# fitnessBuddy-BOTTOM.net
KiCad netlist of a schematic drawn in EAGLE
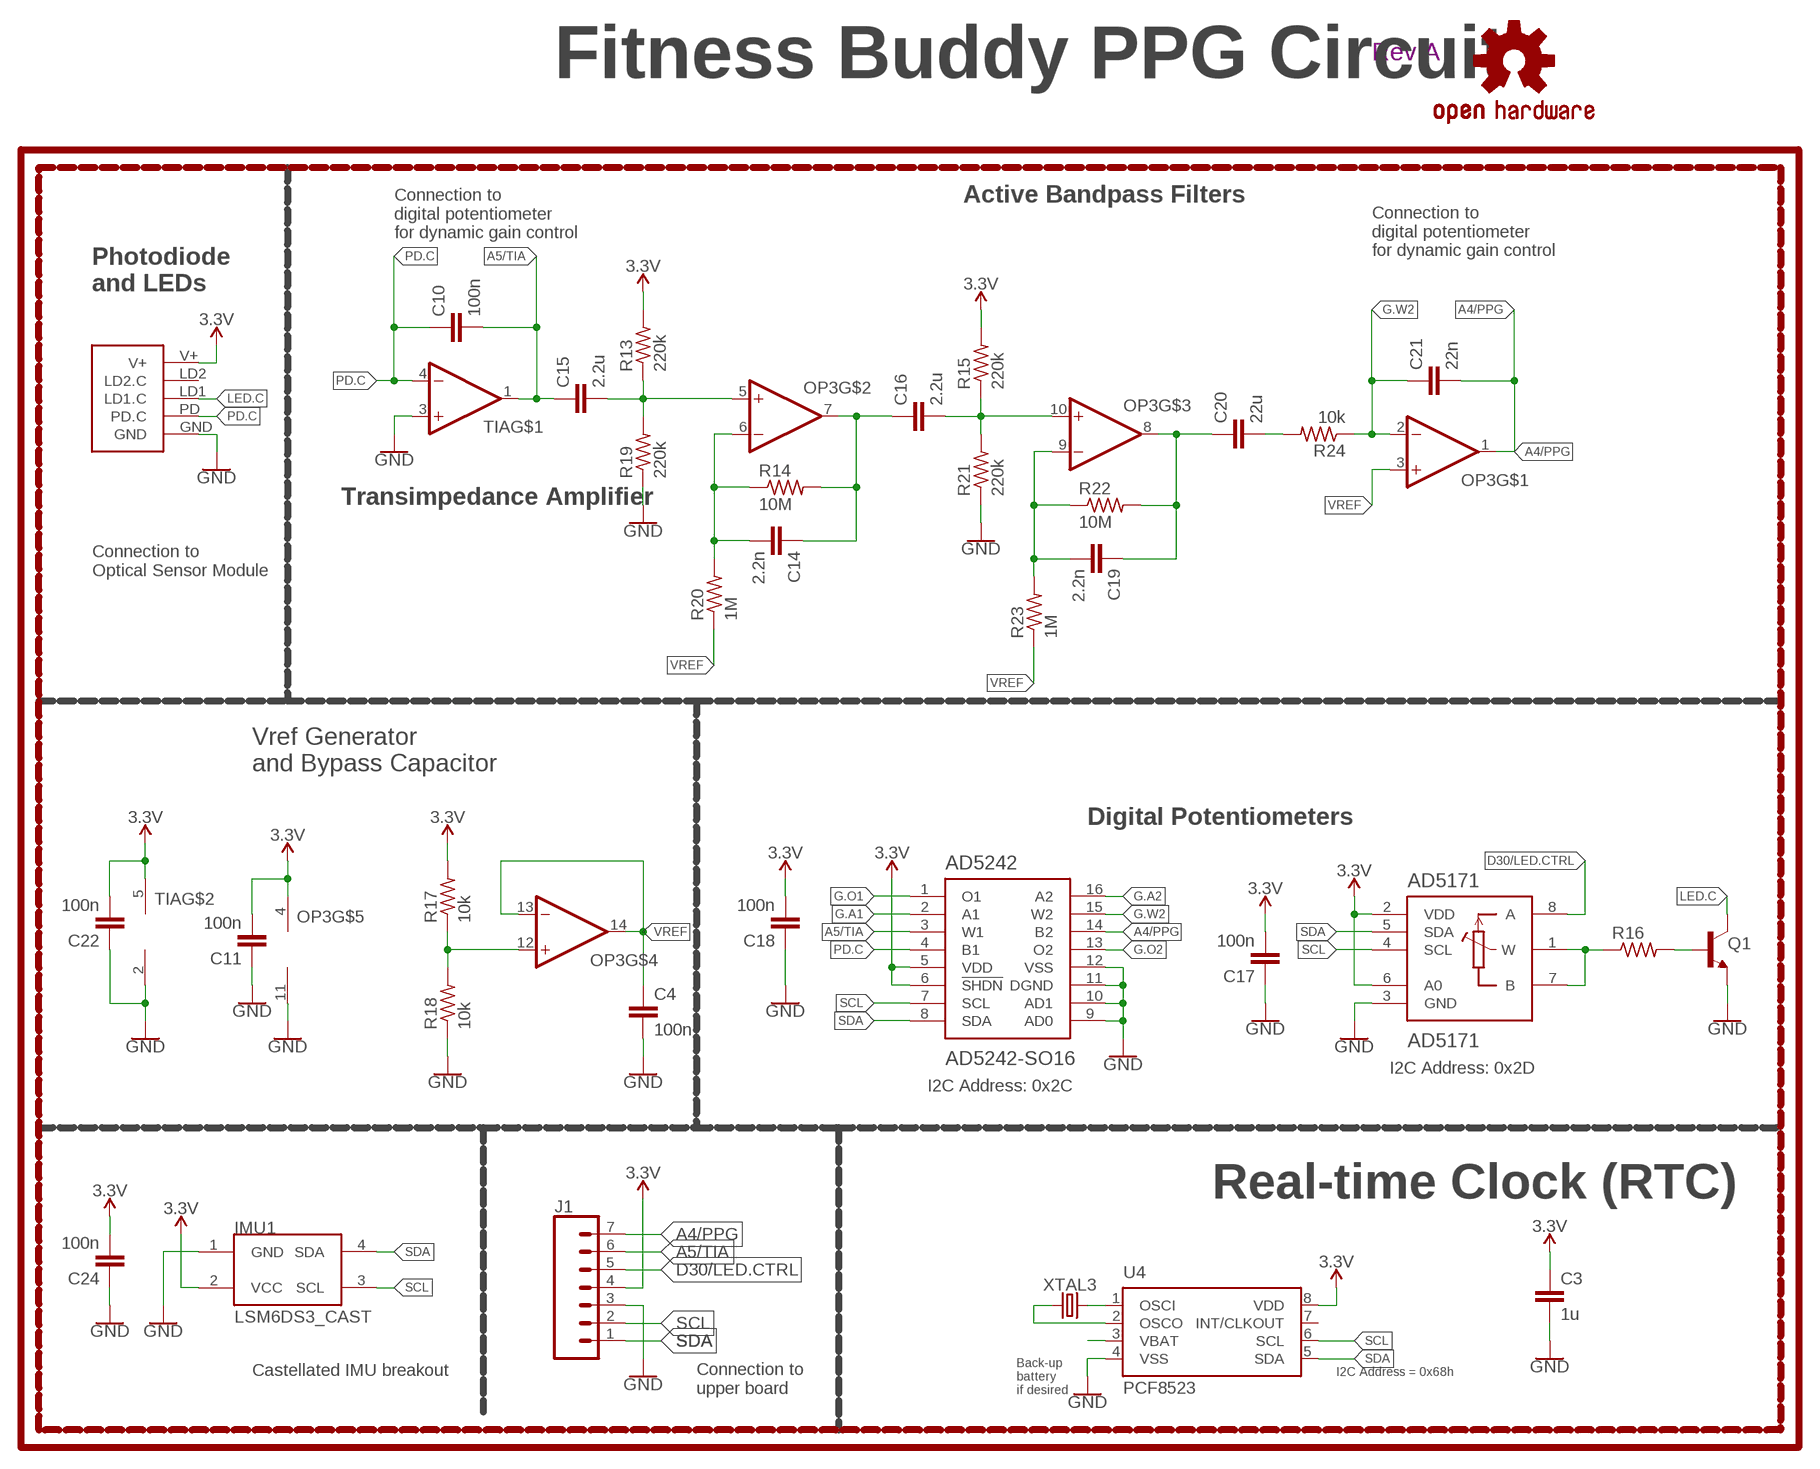
[diagram p0: schematic, sheet 1]

(export (version "E")
  (design (tool "Eeschema 10.0.6"))
  (components
    (comp (ref "AD5171")
      (value "AD5171")
      (footprint "eagle-import:SOT-23-8")
      (libsource (lib "eagle-import") (part "AD5171"))
    )
    (comp (ref "AD5242")
      (value "AD5242-SO16")
      (footprint "eagle-import:SO16")
      (libsource (lib "eagle-import") (part "AD5242-SO16"))
    )
    (comp (ref "C3")
      (value "1u")
      (footprint "eagle-import:C0603")
      (libsource (lib "eagle-import") (part "CAPACITOR0603"))
    )
    (comp (ref "C4")
      (value "100n")
      (footprint "eagle-import:C0603")
      (libsource (lib "eagle-import") (part "CAPACITOR0603"))
    )
    (comp (ref "C10")
      (value "100n")
      (footprint "eagle-import:C0603")
      (libsource (lib "eagle-import") (part "CAPACITOR0603"))
    )
    (comp (ref "C11")
      (value "100n")
      (footprint "eagle-import:C0603")
      (libsource (lib "eagle-import") (part "CAPACITOR0603"))
    )
    (comp (ref "C14")
      (value "2.2n")
      (footprint "eagle-import:C0603")
      (libsource (lib "eagle-import") (part "CAPACITOR0603"))
    )
    (comp (ref "C15")
      (value "2.2u")
      (footprint "eagle-import:C0603")
      (libsource (lib "eagle-import") (part "CAPACITOR0603"))
    )
    (comp (ref "C16")
      (value "2.2u")
      (footprint "eagle-import:C0603")
      (libsource (lib "eagle-import") (part "CAPACITOR0603"))
    )
    (comp (ref "C17")
      (value "100n")
      (footprint "eagle-import:C0603")
      (libsource (lib "eagle-import") (part "CAPACITOR0603"))
    )
    (comp (ref "C18")
      (value "100n")
      (footprint "eagle-import:C0603")
      (libsource (lib "eagle-import") (part "CAPACITOR0603"))
    )
    (comp (ref "C19")
      (value "2.2n")
      (footprint "eagle-import:C0603")
      (libsource (lib "eagle-import") (part "CAPACITOR0603"))
    )
    (comp (ref "C20")
      (value "22u")
      (footprint "eagle-import:C0603")
      (libsource (lib "eagle-import") (part "CAPACITOR0603"))
    )
    (comp (ref "C21")
      (value "22n")
      (footprint "eagle-import:C0603")
      (libsource (lib "eagle-import") (part "CAPACITOR0603"))
    )
    (comp (ref "C22")
      (value "100n")
      (footprint "eagle-import:C0603")
      (libsource (lib "eagle-import") (part "CAPACITOR0603"))
    )
    (comp (ref "C24")
      (value "100n")
      (footprint "eagle-import:C0603")
      (libsource (lib "eagle-import") (part "CAPACITOR0603"))
    )
    (comp (ref "IMU1")
      (value "LSM6DS3_CAST")
      (footprint "eagle-import:LSM6DS3_CAST")
      (libsource (lib "eagle-import") (part "LSM6DS3_CAST"))
    )
    (comp (ref "J1")
      (value "CONN_07-1.27MM")
      (footprint "eagle-import:1X07_1.27MM")
      (libsource (lib "eagle-import") (part "CONN_07-1.27MM"))
    )
    (comp (ref "LOGO1")
      (value "REVISION.A")
      (footprint "eagle-import:REV.A")
      (libsource (lib "eagle-import") (part "REVISION.A"))
    )
    (comp (ref "LOGO2")
      (value "OSHW-LOGOS")
      (footprint "eagle-import:OSHW-LOGO-S")
      (libsource (lib "eagle-import") (part "OSHW-LOGOS"))
    )
    (comp (ref "OP3")
      (value "OP-QUAD-SO14")
      (footprint "eagle-import:SO14")
      (libsource (lib "eagle-import") (part "OP-QUAD-SO14"))
    )
    (comp (ref "Q1")
      (value "NPN-GENERIC")
      (footprint "eagle-import:SOT23-3")
      (libsource (lib "eagle-import") (part "NPN-GENERIC"))
    )
    (comp (ref "R13")
      (value "220k")
      (footprint "eagle-import:R0603")
      (libsource (lib "eagle-import") (part "RESISTOR0603"))
    )
    (comp (ref "R14")
      (value "10M")
      (footprint "eagle-import:R0603")
      (libsource (lib "eagle-import") (part "RESISTOR0603"))
    )
    (comp (ref "R15")
      (value "220k")
      (footprint "eagle-import:R0603")
      (libsource (lib "eagle-import") (part "RESISTOR0603"))
    )
    (comp (ref "R16")
      (value "RESISTOR0603")
      (footprint "eagle-import:R0603")
      (libsource (lib "eagle-import") (part "RESISTOR0603"))
    )
    (comp (ref "R17")
      (value "10k")
      (footprint "eagle-import:R0402")
      (libsource (lib "eagle-import") (part "RESISTOR0402"))
    )
    (comp (ref "R18")
      (value "10k")
      (footprint "eagle-import:R0402")
      (libsource (lib "eagle-import") (part "RESISTOR0402"))
    )
    (comp (ref "R19")
      (value "220k")
      (footprint "eagle-import:R0603")
      (libsource (lib "eagle-import") (part "RESISTOR0603"))
    )
    (comp (ref "R20")
      (value "1M")
      (footprint "eagle-import:R0603")
      (libsource (lib "eagle-import") (part "RESISTOR0603"))
    )
    (comp (ref "R21")
      (value "220k")
      (footprint "eagle-import:R0603")
      (libsource (lib "eagle-import") (part "RESISTOR0603"))
    )
    (comp (ref "R22")
      (value "10M")
      (footprint "eagle-import:R0603")
      (libsource (lib "eagle-import") (part "RESISTOR0603"))
    )
    (comp (ref "R23")
      (value "1M")
      (footprint "eagle-import:R0603")
      (libsource (lib "eagle-import") (part "RESISTOR0603"))
    )
    (comp (ref "R24")
      (value "10k")
      (footprint "eagle-import:R0603")
      (libsource (lib "eagle-import") (part "RESISTOR0603"))
    )
    (comp (ref "TIA")
      (value "OP-SINGLEOT")
      (footprint "eagle-import:SOT23-5")
      (libsource (lib "eagle-import") (part "OP-SINGLEOT"))
    )
    (comp (ref "U$3")
      (value "PPG.MODULE.2")
      (footprint "eagle-import:PPG.MODULE.2")
      (libsource (lib "eagle-import") (part "PPG.MODULE.2"))
    )
    (comp (ref "U4")
      (value "PCF8523")
      (footprint "eagle-import:SO8")
      (libsource (lib "eagle-import") (part "PCF8523"))
    )
    (comp (ref "XTAL3")
      (value "32.7680kHz")
      (footprint "eagle-import:2-SMD.NOLEAD.2.0MMTO1.2MM")
      (libsource (lib "eagle-import") (part "CRYSTALECS-.327-12.5-12-C-TR"))
    )
  )
  (nets
    (net (code "1") (name "3.3V") (class "Default")
      (node (ref "AD5171") (pin "2") (pinfunction "VDD_2") (pintype "bidirectional"))
      (node (ref "AD5171") (pin "6") (pinfunction "A0_6") (pintype "bidirectional"))
      (node (ref "AD5242") (pin "5") (pinfunction "VDD_5") (pintype "bidirectional"))
      (node (ref "AD5242") (pin "6") (pinfunction "~{SHDN}_6") (pintype "bidirectional"))
      (node (ref "C11") (pin "2") (pinfunction "2_2") (pintype "passive"))
      (node (ref "C17") (pin "2") (pinfunction "2_2") (pintype "passive"))
      (node (ref "C18") (pin "2") (pinfunction "2_2") (pintype "passive"))
      (node (ref "C22") (pin "2") (pinfunction "2_2") (pintype "passive"))
      (node (ref "C24") (pin "2") (pinfunction "2_2") (pintype "passive"))
      (node (ref "C3") (pin "1") (pinfunction "1_1") (pintype "passive"))
      (node (ref "IMU1") (pin "2") (pinfunction "VCC_2") (pintype "bidirectional"))
      (node (ref "J1") (pin "4") (pinfunction "4_4") (pintype "passive"))
      (node (ref "OP3") (pin "4") (pinfunction "V+_4") (pintype "power_in"))
      (node (ref "R13") (pin "2") (pinfunction "2_2") (pintype "passive"))
      (node (ref "R15") (pin "2") (pinfunction "2_2") (pintype "passive"))
      (node (ref "R17") (pin "2") (pinfunction "2_2") (pintype "passive"))
      (node (ref "TIA") (pin "5") (pinfunction "V+_5") (pintype "power_in"))
      (node (ref "U$3") (pin "V+") (pinfunction "V+_V+") (pintype "bidirectional"))
      (node (ref "U4") (pin "8") (pinfunction "VDD_8") (pintype "power_in"))
    )
    (net (code "2") (name "A4{slash}PPG") (class "Default")
      (node (ref "AD5242") (pin "14") (pinfunction "B2_14") (pintype "bidirectional"))
      (node (ref "C21") (pin "2") (pinfunction "2_2") (pintype "passive"))
      (node (ref "J1") (pin "7") (pinfunction "7_7") (pintype "passive"))
      (node (ref "OP3") (pin "1") (pinfunction "OUT_1") (pintype "output"))
    )
    (net (code "3") (name "A5{slash}TIA") (class "Default")
      (node (ref "AD5242") (pin "3") (pinfunction "W1_3") (pintype "bidirectional"))
      (node (ref "C10") (pin "2") (pinfunction "2_2") (pintype "passive"))
      (node (ref "C15") (pin "1") (pinfunction "1_1") (pintype "passive"))
      (node (ref "J1") (pin "6") (pinfunction "6_6") (pintype "passive"))
      (node (ref "TIA") (pin "1") (pinfunction "OUT_1") (pintype "output"))
    )
    (net (code "4") (name "D30{slash}LED.CTRL") (class "Default")
      (node (ref "AD5171") (pin "8") (pinfunction "A_8") (pintype "bidirectional"))
      (node (ref "J1") (pin "5") (pinfunction "5_5") (pintype "passive"))
    )
    (net (code "5") (name "G.A1") (class "Default")
      (node (ref "AD5242") (pin "2") (pinfunction "A1_2") (pintype "bidirectional"))
    )
    (net (code "6") (name "G.A2") (class "Default")
      (node (ref "AD5242") (pin "16") (pinfunction "A2_16") (pintype "bidirectional"))
    )
    (net (code "7") (name "G.O1") (class "Default")
      (node (ref "AD5242") (pin "1") (pinfunction "O1_1") (pintype "bidirectional"))
    )
    (net (code "8") (name "G.O2") (class "Default")
      (node (ref "AD5242") (pin "13") (pinfunction "O2_13") (pintype "bidirectional"))
    )
    (net (code "9") (name "G.W2") (class "Default")
      (node (ref "AD5242") (pin "15") (pinfunction "W2_15") (pintype "bidirectional"))
      (node (ref "C21") (pin "1") (pinfunction "1_1") (pintype "passive"))
      (node (ref "OP3") (pin "2") (pinfunction "-IN_2") (pintype "input"))
      (node (ref "R24") (pin "1") (pinfunction "1_1") (pintype "passive"))
    )
    (net (code "10") (name "GND") (class "Default")
      (node (ref "AD5171") (pin "3") (pinfunction "GND_3") (pintype "bidirectional"))
      (node (ref "AD5242") (pin "10") (pinfunction "AD1_10") (pintype "bidirectional"))
      (node (ref "AD5242") (pin "11") (pinfunction "DGND_11") (pintype "bidirectional"))
      (node (ref "AD5242") (pin "12") (pinfunction "VSS_12") (pintype "bidirectional"))
      (node (ref "AD5242") (pin "9") (pinfunction "AD0_9") (pintype "bidirectional"))
      (node (ref "C11") (pin "1") (pinfunction "1_1") (pintype "passive"))
      (node (ref "C17") (pin "1") (pinfunction "1_1") (pintype "passive"))
      (node (ref "C18") (pin "1") (pinfunction "1_1") (pintype "passive"))
      (node (ref "C22") (pin "1") (pinfunction "1_1") (pintype "passive"))
      (node (ref "C24") (pin "1") (pinfunction "1_1") (pintype "passive"))
      (node (ref "C3") (pin "2") (pinfunction "2_2") (pintype "passive"))
      (node (ref "C4") (pin "2") (pinfunction "2_2") (pintype "passive"))
      (node (ref "IMU1") (pin "1") (pinfunction "GND_1") (pintype "bidirectional"))
      (node (ref "J1") (pin "3") (pinfunction "3_3") (pintype "passive"))
      (node (ref "OP3") (pin "11") (pinfunction "V-_11") (pintype "power_in"))
      (node (ref "Q1") (pin "2") (pinfunction "E_2") (pintype "passive"))
      (node (ref "R18") (pin "1") (pinfunction "1_1") (pintype "passive"))
      (node (ref "R19") (pin "1") (pinfunction "1_1") (pintype "passive"))
      (node (ref "R21") (pin "1") (pinfunction "1_1") (pintype "passive"))
      (node (ref "TIA") (pin "2") (pinfunction "V-_2") (pintype "power_in"))
      (node (ref "TIA") (pin "3") (pinfunction "+IN_3") (pintype "input"))
      (node (ref "U$3") (pin "GND") (pinfunction "GND_GND") (pintype "bidirectional"))
      (node (ref "U4") (pin "4") (pinfunction "VSS_4") (pintype "power_in"))
    )
    (net (code "11") (name "LED.C") (class "Default")
      (node (ref "Q1") (pin "3") (pinfunction "C_3") (pintype "passive"))
      (node (ref "U$3") (pin "LD1") (pinfunction "LD1.C_LD1") (pintype "bidirectional"))
    )
    (net (code "12") (name "Net-(AD5171-B)") (class "Default")
      (node (ref "AD5171") (pin "1") (pinfunction "W_1") (pintype "bidirectional"))
      (node (ref "AD5171") (pin "7") (pinfunction "B_7") (pintype "bidirectional"))
      (node (ref "R16") (pin "1") (pinfunction "1_1") (pintype "passive"))
    )
    (net (code "13") (name "Net-(C20-Pad2)") (class "Default")
      (node (ref "C20") (pin "2") (pinfunction "2_2") (pintype "passive"))
      (node (ref "R24") (pin "2") (pinfunction "2_2") (pintype "passive"))
    )
    (net (code "14") (name "Net-(OP3B-+IN)") (class "Default")
      (node (ref "C15") (pin "2") (pinfunction "2_2") (pintype "passive"))
      (node (ref "OP3") (pin "5") (pinfunction "+IN_5") (pintype "input"))
      (node (ref "R13") (pin "1") (pinfunction "1_1") (pintype "passive"))
      (node (ref "R19") (pin "2") (pinfunction "2_2") (pintype "passive"))
    )
    (net (code "15") (name "Net-(OP3B--IN)") (class "Default")
      (node (ref "C14") (pin "2") (pinfunction "2_2") (pintype "passive"))
      (node (ref "OP3") (pin "6") (pinfunction "-IN_6") (pintype "input"))
      (node (ref "R14") (pin "1") (pinfunction "1_1") (pintype "passive"))
      (node (ref "R20") (pin "2") (pinfunction "2_2") (pintype "passive"))
    )
    (net (code "16") (name "Net-(OP3B-OUT)") (class "Default")
      (node (ref "C14") (pin "1") (pinfunction "1_1") (pintype "passive"))
      (node (ref "C16") (pin "1") (pinfunction "1_1") (pintype "passive"))
      (node (ref "OP3") (pin "7") (pinfunction "OUT_7") (pintype "output"))
      (node (ref "R14") (pin "2") (pinfunction "2_2") (pintype "passive"))
    )
    (net (code "17") (name "Net-(OP3C-+IN)") (class "Default")
      (node (ref "C16") (pin "2") (pinfunction "2_2") (pintype "passive"))
      (node (ref "OP3") (pin "10") (pinfunction "+IN_10") (pintype "input"))
      (node (ref "R15") (pin "1") (pinfunction "1_1") (pintype "passive"))
      (node (ref "R21") (pin "2") (pinfunction "2_2") (pintype "passive"))
    )
    (net (code "18") (name "Net-(OP3C--IN)") (class "Default")
      (node (ref "C19") (pin "2") (pinfunction "2_2") (pintype "passive"))
      (node (ref "OP3") (pin "9") (pinfunction "-IN_9") (pintype "input"))
      (node (ref "R22") (pin "1") (pinfunction "1_1") (pintype "passive"))
      (node (ref "R23") (pin "2") (pinfunction "2_2") (pintype "passive"))
    )
    (net (code "19") (name "Net-(OP3C-OUT)") (class "Default")
      (node (ref "C19") (pin "1") (pinfunction "1_1") (pintype "passive"))
      (node (ref "C20") (pin "1") (pinfunction "1_1") (pintype "passive"))
      (node (ref "OP3") (pin "8") (pinfunction "OUT_8") (pintype "output"))
      (node (ref "R22") (pin "2") (pinfunction "2_2") (pintype "passive"))
    )
    (net (code "20") (name "Net-(OP3D-+IN)") (class "Default")
      (node (ref "OP3") (pin "12") (pinfunction "+IN_12") (pintype "input"))
      (node (ref "R17") (pin "1") (pinfunction "1_1") (pintype "passive"))
      (node (ref "R18") (pin "2") (pinfunction "2_2") (pintype "passive"))
    )
    (net (code "21") (name "Net-(Q1-B)") (class "Default")
      (node (ref "Q1") (pin "1") (pinfunction "B_1") (pintype "passive"))
      (node (ref "R16") (pin "2") (pinfunction "2_2") (pintype "passive"))
    )
    (net (code "22") (name "Net-(U4-OSCI)") (class "Default")
      (node (ref "U4") (pin "1") (pinfunction "OSCI_1") (pintype "bidirectional"))
      (node (ref "XTAL3") (pin "P$2") (pinfunction "2_P$2") (pintype "passive"))
    )
    (net (code "23") (name "Net-(U4-OSCO)") (class "Default")
      (node (ref "U4") (pin "2") (pinfunction "OSCO_2") (pintype "bidirectional"))
      (node (ref "XTAL3") (pin "P$1") (pinfunction "1_P$1") (pintype "passive"))
    )
    (net (code "24") (name "PD.C") (class "Default")
      (node (ref "AD5242") (pin "4") (pinfunction "B1_4") (pintype "bidirectional"))
      (node (ref "C10") (pin "1") (pinfunction "1_1") (pintype "passive"))
      (node (ref "TIA") (pin "4") (pinfunction "-IN_4") (pintype "input"))
      (node (ref "U$3") (pin "PD") (pinfunction "PD.C_PD") (pintype "bidirectional"))
    )
    (net (code "25") (name "SCL") (class "Default")
      (node (ref "AD5171") (pin "4") (pinfunction "SCL_4") (pintype "bidirectional"))
      (node (ref "AD5242") (pin "7") (pinfunction "SCL_7") (pintype "bidirectional"))
      (node (ref "IMU1") (pin "3") (pinfunction "SCL_3") (pintype "bidirectional"))
      (node (ref "J1") (pin "2") (pinfunction "2_2") (pintype "passive"))
      (node (ref "U4") (pin "6") (pinfunction "SCL_6") (pintype "bidirectional"))
    )
    (net (code "26") (name "SDA") (class "Default")
      (node (ref "AD5171") (pin "5") (pinfunction "SDA_5") (pintype "bidirectional"))
      (node (ref "AD5242") (pin "8") (pinfunction "SDA_8") (pintype "bidirectional"))
      (node (ref "IMU1") (pin "4") (pinfunction "SDA_4") (pintype "bidirectional"))
      (node (ref "J1") (pin "1") (pinfunction "1_1") (pintype "passive"))
      (node (ref "U4") (pin "5") (pinfunction "SDA_5") (pintype "bidirectional"))
    )
    (net (code "27") (name "VREF") (class "Default")
      (node (ref "C4") (pin "1") (pinfunction "1_1") (pintype "passive"))
      (node (ref "OP3") (pin "13") (pinfunction "-IN_13") (pintype "input"))
      (node (ref "OP3") (pin "14") (pinfunction "OUT_14") (pintype "output"))
      (node (ref "OP3") (pin "3") (pinfunction "+IN_3") (pintype "input"))
      (node (ref "R20") (pin "1") (pinfunction "1_1") (pintype "passive"))
      (node (ref "R23") (pin "1") (pinfunction "1_1") (pintype "passive"))
    )
    (net (code "28") (name "unconnected-(U$3-LD2.C-PadLD2)") (class "Default")
      (node (ref "U$3") (pin "LD2") (pinfunction "LD2.C_LD2") (pintype "bidirectional"))
    )
    (net (code "29") (name "unconnected-(U4-INT{slash}CLKOUT-Pad7)") (class "Default")
      (node (ref "U4") (pin "7") (pinfunction "INT/CLKOUT_7") (pintype "bidirectional"))
    )
    (net (code "30") (name "unconnected-(U4-VBAT-Pad3)") (class "Default")
      (node (ref "U4") (pin "3") (pinfunction "VBAT_3") (pintype "power_in"))
    )
  )
)
